# Climber.net
KiCad netlist of a schematic drawn in EAGLE
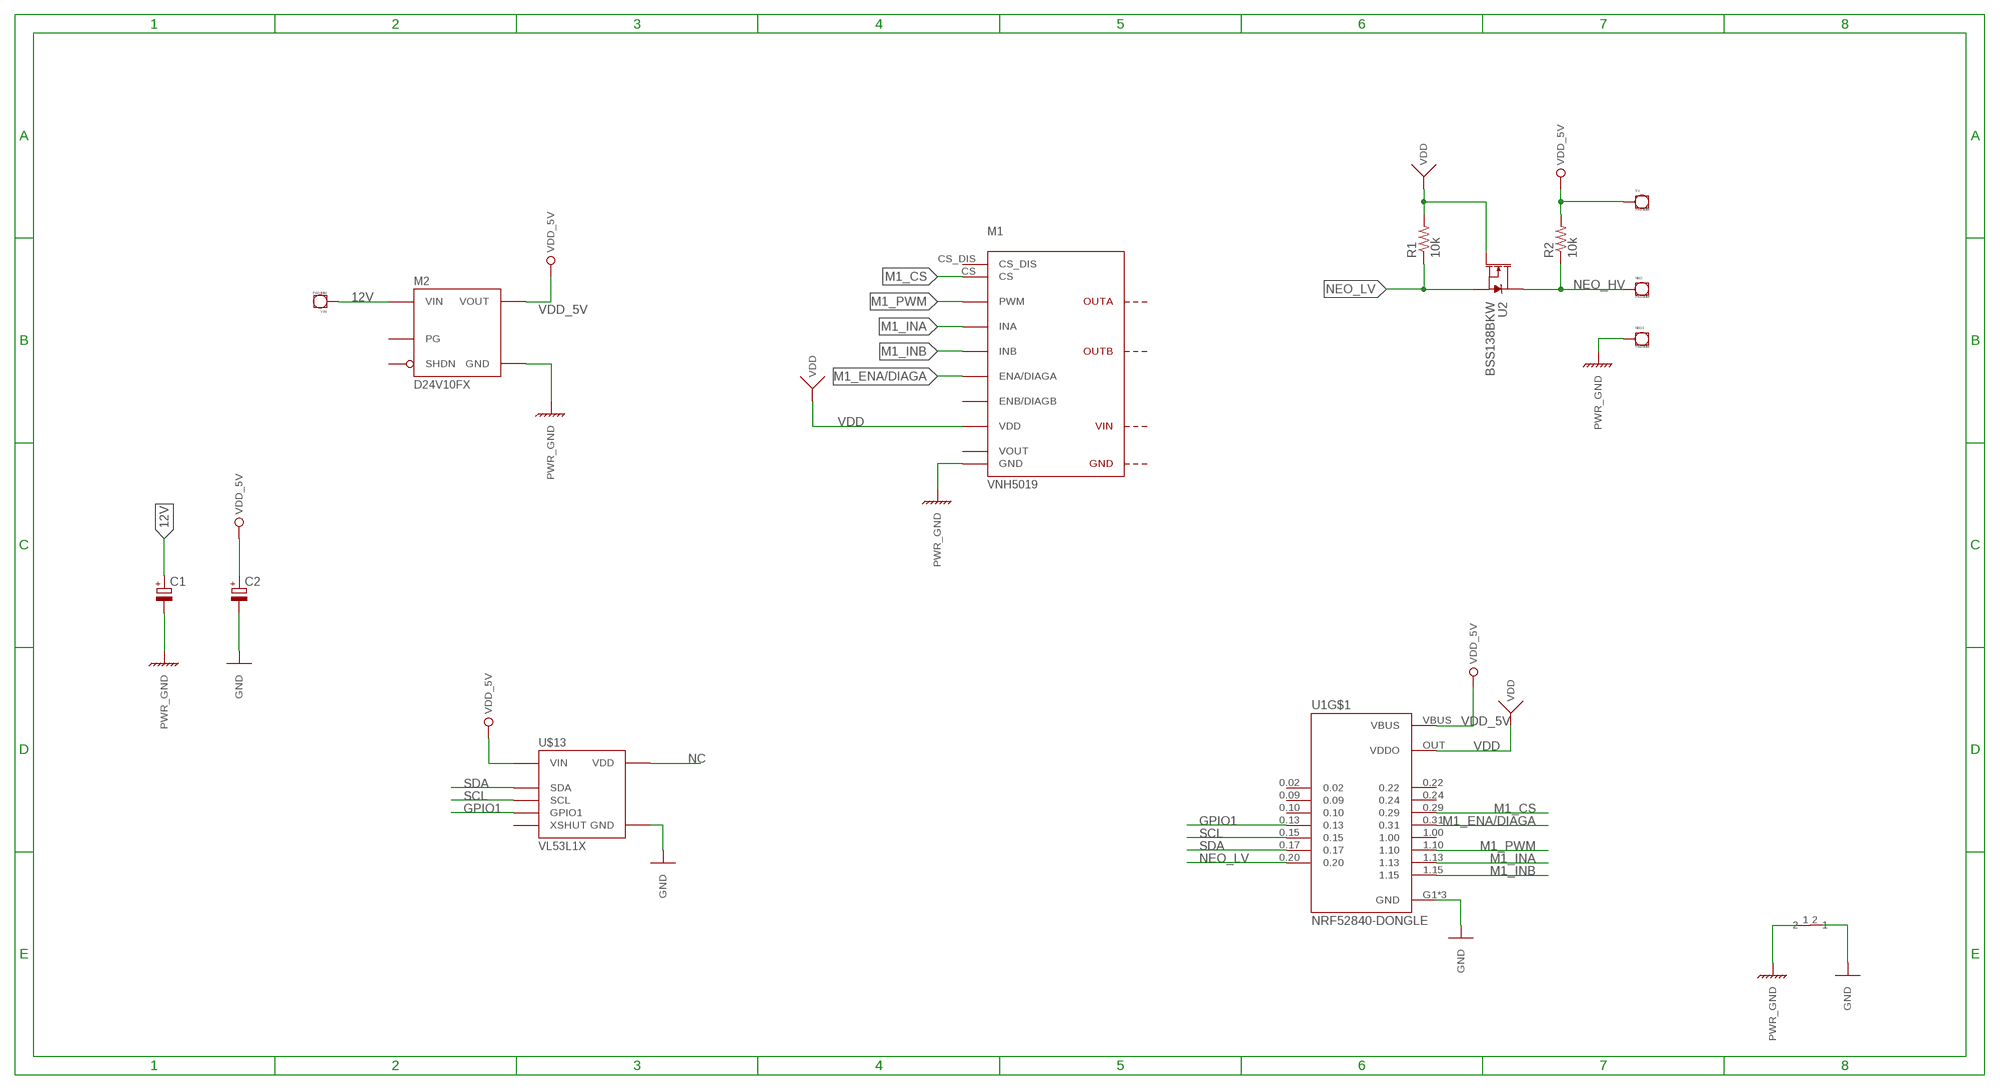
[diagram p0: schematic, sheet 1]

(export (version "E")
  (design (tool "Eeschema 10.0.6"))
  (components
    (comp (ref "5V")
      (value "PAD3MM")
      (footprint "eagle-import:PAD_3")
      (libsource (lib "eagle-import") (part "PAD3MM"))
    )
    (comp (ref "C1")
      (value "CPOL-EUE5-4")
      (footprint "eagle-import:E5-4")
      (libsource (lib "eagle-import") (part "CPOL-EUE5-4"))
    )
    (comp (ref "C2")
      (value "CPOL-EUE5-4")
      (footprint "eagle-import:E5-4")
      (libsource (lib "eagle-import") (part "CPOL-EUE5-4"))
    )
    (comp (ref "M1")
      (value "VNH5019")
      (footprint "eagle-import:VNH5019")
      (libsource (lib "eagle-import") (part "VNH5019"))
    )
    (comp (ref "M2")
      (value "D24V10FX")
      (footprint "eagle-import:D24V10FX")
      (libsource (lib "eagle-import") (part "D24V10FX"))
    )
    (comp (ref "NEO")
      (value "PAD3MM")
      (footprint "eagle-import:PAD_3")
      (libsource (lib "eagle-import") (part "PAD3MM"))
    )
    (comp (ref "NEO1")
      (value "PAD3MM")
      (footprint "eagle-import:PAD_3")
      (libsource (lib "eagle-import") (part "PAD3MM"))
    )
    (comp (ref "R1")
      (value "10k")
      (footprint "eagle-import:R0603")
      (libsource (lib "eagle-import") (part "R-US_R0603"))
    )
    (comp (ref "R2")
      (value "10k")
      (footprint "eagle-import:R0603")
      (libsource (lib "eagle-import") (part "R-US_R0603"))
    )
    (comp (ref "U$10")
      (value "NET_CONN")
      (footprint "eagle-import:NET_CONN")
      (libsource (lib "eagle-import") (part "NET_CONN"))
    )
    (comp (ref "U$13")
      (value "VL53L1X")
      (footprint "eagle-import:VL53L1X")
      (libsource (lib "eagle-import") (part "VL53L1X"))
    )
    (comp (ref "U1")
      (value "NRF52840-DONGLE")
      (footprint "eagle-import:MODULE_NRF52840-DONGLE")
      (fields (field (name "MF") "Nordic Semiconductor"))
      (libsource (lib "eagle-import") (part "NRF52840-DONGLE"))
    )
    (comp (ref "U2")
      (value "BSS138BKW")
      (footprint "eagle-import:SOT65P210X110-3N")
      (libsource (lib "eagle-import") (part "BSS138BKW"))
    )
    (comp (ref "VIN")
      (value "PAD3MM")
      (footprint "eagle-import:PAD_3")
      (libsource (lib "eagle-import") (part "PAD3MM"))
    )
  )
  (nets
    (net (code "1") (name "/GPIO1") (class "Default")
      (node (ref "U$13") (pin "GPIO1") (pinfunction "GPIO1_GPIO1") (pintype "output"))
      (node (ref "U1") (pin "0.13") (pinfunction "0.13_0.13") (pintype "bidirectional"))
    )
    (net (code "2") (name "/NC") (class "Default")
      (node (ref "U$13") (pin "VDD") (pinfunction "VDD_VDD") (pintype "power_in"))
    )
    (net (code "3") (name "/NEO_HV") (class "Default")
      (node (ref "NEO") (pin "P$1") (pinfunction "1_P$1") (pintype "passive"))
      (node (ref "R2") (pin "1") (pinfunction "1_1") (pintype "passive"))
      (node (ref "U2") (pin "3") (pinfunction "D_3") (pintype "bidirectional"))
    )
    (net (code "4") (name "/SCL") (class "Default")
      (node (ref "U$13") (pin "SCL") (pinfunction "SCL_SCL") (pintype "output"))
      (node (ref "U1") (pin "0.15") (pinfunction "0.15_0.15") (pintype "bidirectional"))
    )
    (net (code "5") (name "/SDA") (class "Default")
      (node (ref "U$13") (pin "SDA") (pinfunction "SDA_SDA") (pintype "output"))
      (node (ref "U1") (pin "0.17") (pinfunction "0.17_0.17") (pintype "bidirectional"))
    )
    (net (code "6") (name "/VOUT") (class "Default")
      (node (ref "M1") (pin "VOUT") (pinfunction "VOUT_VOUT") (pintype "power_in"))
    )
    (net (code "7") (name "5V") (class "Default")
      (node (ref "M1") (pin "VDD") (pinfunction "VDD_VDD") (pintype "power_in"))
      (node (ref "R1") (pin "2") (pinfunction "2_2") (pintype "passive"))
      (node (ref "U1") (pin "OUT") (pinfunction "VDDO_OUT") (pintype "output"))
      (node (ref "U2") (pin "1") (pinfunction "G_1") (pintype "bidirectional"))
    )
    (net (code "8") (name "12V") (class "Default")
      (node (ref "C1") (pin "+") (pinfunction "+_+") (pintype "passive"))
      (node (ref "M2") (pin "VIN") (pinfunction "VIN_VIN") (pintype "power_in"))
      (node (ref "VIN") (pin "P$1") (pinfunction "1_P$1") (pintype "passive"))
    )
    (net (code "9") (name "GND") (class "Default")
      (node (ref "C2") (pin "-") (pinfunction "-_-") (pintype "passive"))
      (node (ref "U$10") (pin "2") (pinfunction "2_2") (pintype "bidirectional"))
      (node (ref "U$13") (pin "GND") (pinfunction "GND_GND") (pintype "power_in"))
      (node (ref "U1") (pin "G1") (pinfunction "GND_G1") (pintype "power_in"))
      (node (ref "U1") (pin "G2") (pinfunction "GND_G2") (pintype "power_in"))
      (node (ref "U1") (pin "G3") (pinfunction "GND_G3") (pintype "power_in"))
    )
    (net (code "10") (name "GNDIN") (class "Default")
      (node (ref "C1") (pin "-") (pinfunction "-_-") (pintype "passive"))
      (node (ref "M1") (pin "GND@0") (pinfunction "GND_GND@0") (pintype "power_in"))
      (node (ref "M1") (pin "GND@1") (pinfunction "GND_GND@1") (pintype "power_in"))
      (node (ref "M2") (pin "GND") (pinfunction "GND_GND") (pintype "power_in"))
      (node (ref "NEO1") (pin "P$1") (pinfunction "1_P$1") (pintype "passive"))
      (node (ref "U$10") (pin "1") (pinfunction "1_1") (pintype "bidirectional"))
    )
    (net (code "11") (name "M1_CS") (class "Default")
      (node (ref "M1") (pin "CS") (pinfunction "CS_CS") (pintype "bidirectional"))
      (node (ref "U1") (pin "0.29") (pinfunction "0.29_0.29") (pintype "bidirectional"))
    )
    (net (code "12") (name "M1_ENA{slash}DIAGA") (class "Default")
      (node (ref "M1") (pin "ENA") (pinfunction "ENA/DIAGA_ENA") (pintype "open_collector"))
      (node (ref "U1") (pin "0.31") (pinfunction "0.31_0.31") (pintype "bidirectional"))
    )
    (net (code "13") (name "M1_INA") (class "Default")
      (node (ref "M1") (pin "INA") (pinfunction "INA_INA") (pintype "input"))
      (node (ref "U1") (pin "1.13") (pinfunction "1.13_1.13") (pintype "bidirectional"))
    )
    (net (code "14") (name "M1_INB") (class "Default")
      (node (ref "M1") (pin "INB") (pinfunction "INB_INB") (pintype "input"))
      (node (ref "U1") (pin "1.15") (pinfunction "1.15_1.15") (pintype "bidirectional"))
    )
    (net (code "15") (name "M1_PWM") (class "Default")
      (node (ref "M1") (pin "PWM") (pinfunction "PWM_PWM") (pintype "input"))
      (node (ref "U1") (pin "1.10") (pinfunction "1.10_1.10") (pintype "bidirectional"))
    )
    (net (code "16") (name "NEO_LV") (class "Default")
      (node (ref "R1") (pin "1") (pinfunction "1_1") (pintype "passive"))
      (node (ref "U1") (pin "0.20") (pinfunction "0.20_0.20") (pintype "bidirectional"))
      (node (ref "U2") (pin "2") (pinfunction "S_2") (pintype "bidirectional"))
    )
    (net (code "17") (name "VDD_5V") (class "Default")
      (node (ref "5V") (pin "P$1") (pinfunction "1_P$1") (pintype "passive"))
      (node (ref "C2") (pin "+") (pinfunction "+_+") (pintype "passive"))
      (node (ref "M2") (pin "VOUT") (pinfunction "VOUT_VOUT") (pintype "output"))
      (node (ref "R2") (pin "2") (pinfunction "2_2") (pintype "passive"))
      (node (ref "U$13") (pin "VIN") (pinfunction "VIN_VIN") (pintype "power_in"))
      (node (ref "U1") (pin "VBUS") (pinfunction "VBUS_VBUS") (pintype "power_in"))
    )
    (net (code "18") (name "unconnected-(M1-ENB{slash}DIAGB-PadENB)") (class "Default")
      (node (ref "M1") (pin "ENB") (pinfunction "ENB/DIAGB_ENB") (pintype "open_collector"))
    )
    (net (code "19") (name "unconnected-(M1-PadCS_DIS)") (class "Default")
      (node (ref "M1") (pin "CS_DIS") (pinfunction "CS_DIS_CS_DIS") (pintype "bidirectional"))
    )
    (net (code "20") (name "unconnected-(M2-PadPG)") (class "Default")
      (node (ref "M2") (pin "PG") (pinfunction "PG_PG") (pintype "output"))
    )
    (net (code "21") (name "unconnected-(M2-SHDN-Pad!SHDN)") (class "Default")
      (node (ref "M2") (pin "!SHDN") (pinfunction "SHDN_!SHDN") (pintype "input"))
    )
    (net (code "22") (name "unconnected-(U$13-PadXSHUT)") (class "Default")
      (node (ref "U$13") (pin "XSHUT") (pinfunction "XSHUT_XSHUT") (pintype "input"))
    )
    (net (code "23") (name "unconnected-(U1-Pad0.02)") (class "Default")
      (node (ref "U1") (pin "0.02") (pinfunction "0.02_0.02") (pintype "bidirectional"))
    )
    (net (code "24") (name "unconnected-(U1-Pad0.09)") (class "Default")
      (node (ref "U1") (pin "0.09") (pinfunction "0.09_0.09") (pintype "bidirectional"))
    )
    (net (code "25") (name "unconnected-(U1-Pad0.10)") (class "Default")
      (node (ref "U1") (pin "0.10") (pinfunction "0.10_0.10") (pintype "bidirectional"))
    )
    (net (code "26") (name "unconnected-(U1-Pad0.22)") (class "Default")
      (node (ref "U1") (pin "0.22") (pinfunction "0.22_0.22") (pintype "bidirectional"))
    )
    (net (code "27") (name "unconnected-(U1-Pad0.24)") (class "Default")
      (node (ref "U1") (pin "0.24") (pinfunction "0.24_0.24") (pintype "bidirectional"))
    )
    (net (code "28") (name "unconnected-(U1-Pad1.00)") (class "Default")
      (node (ref "U1") (pin "1.00") (pinfunction "1.00_1.00") (pintype "bidirectional"))
    )
  )
)
